# 16nMod4.net
KiCad netlist of a schematic drawn in EAGLE
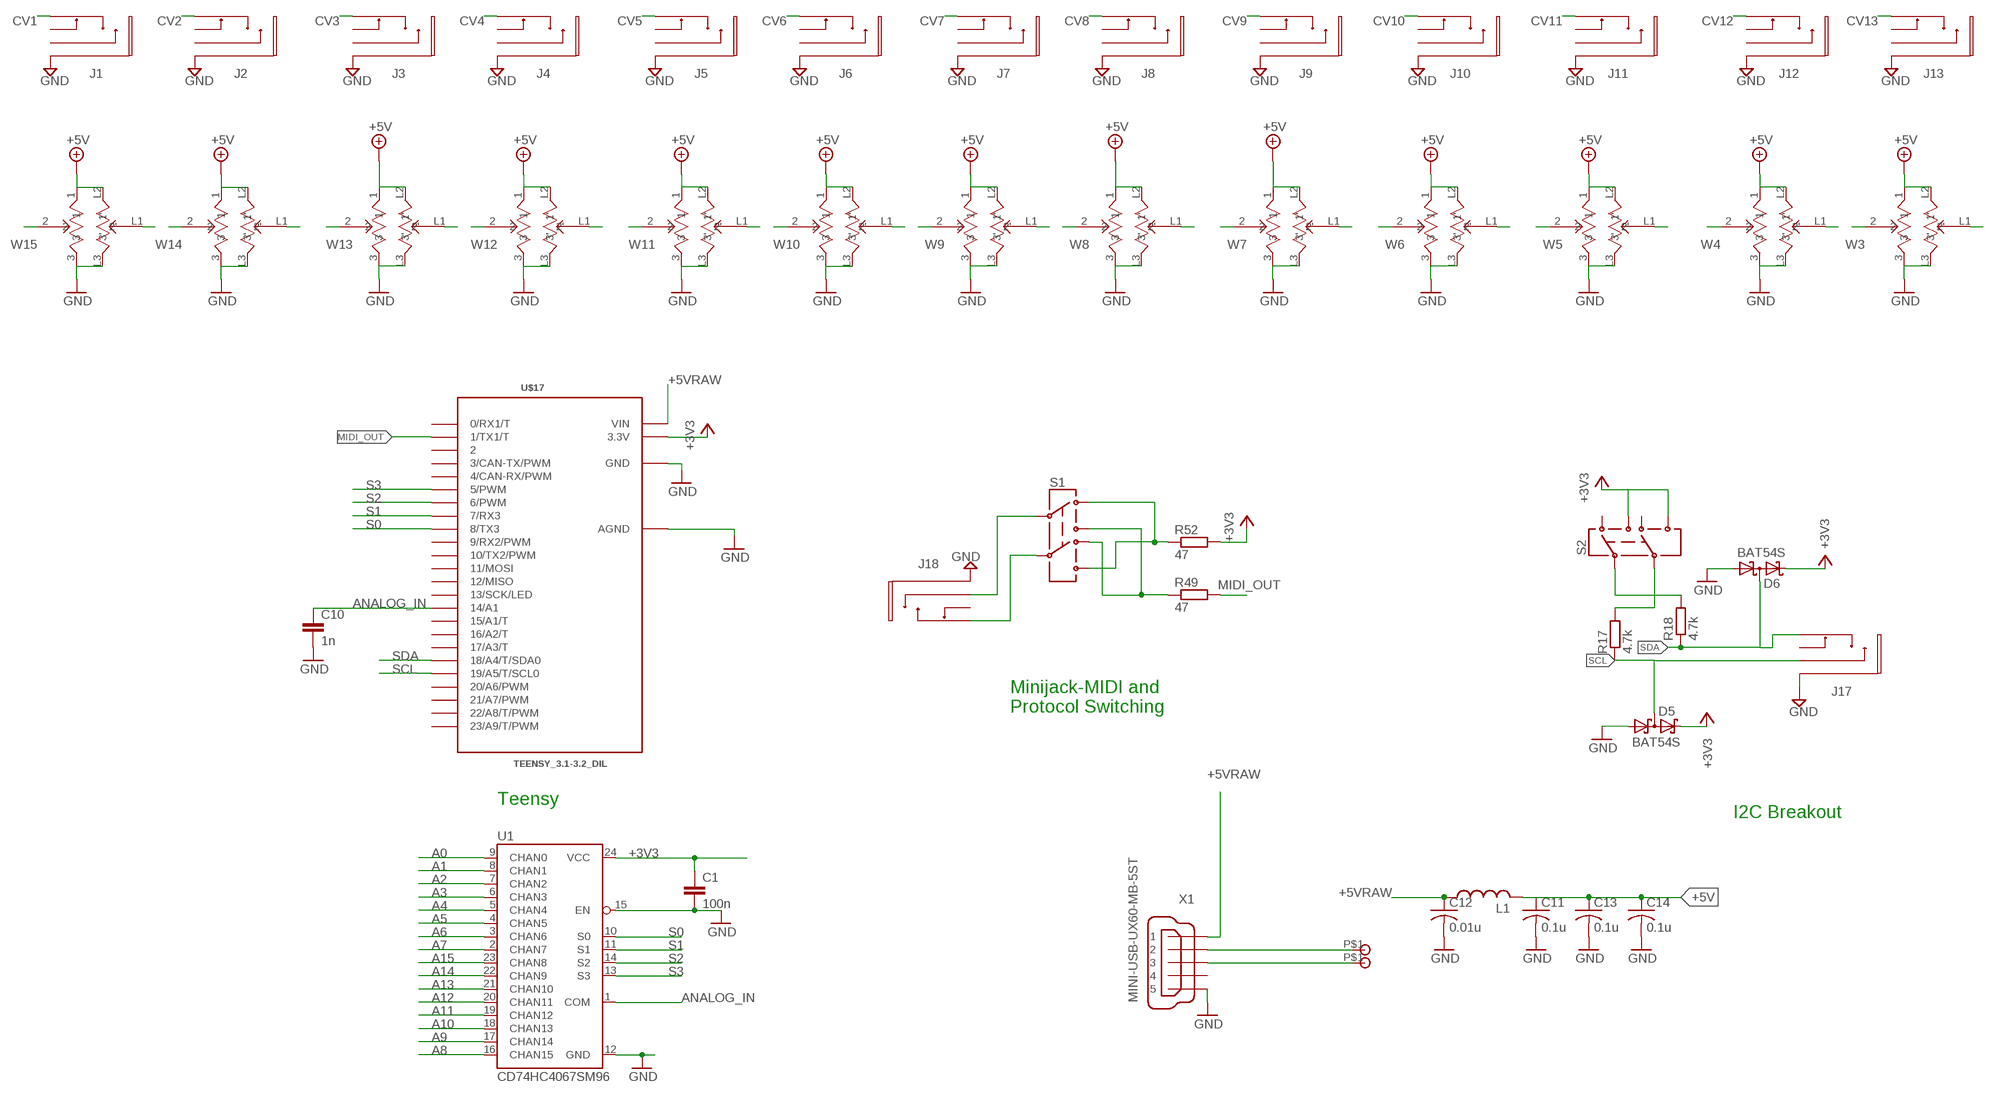
[diagram p0: schematic, sheet 1, part 1 of 2]
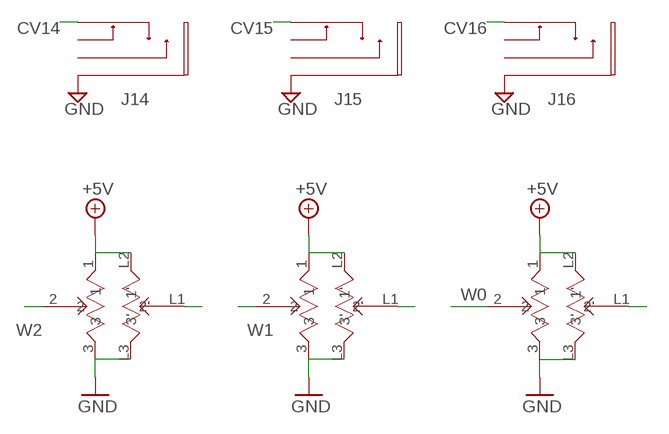
[diagram p1: schematic, sheet 1, part 2 of 2]
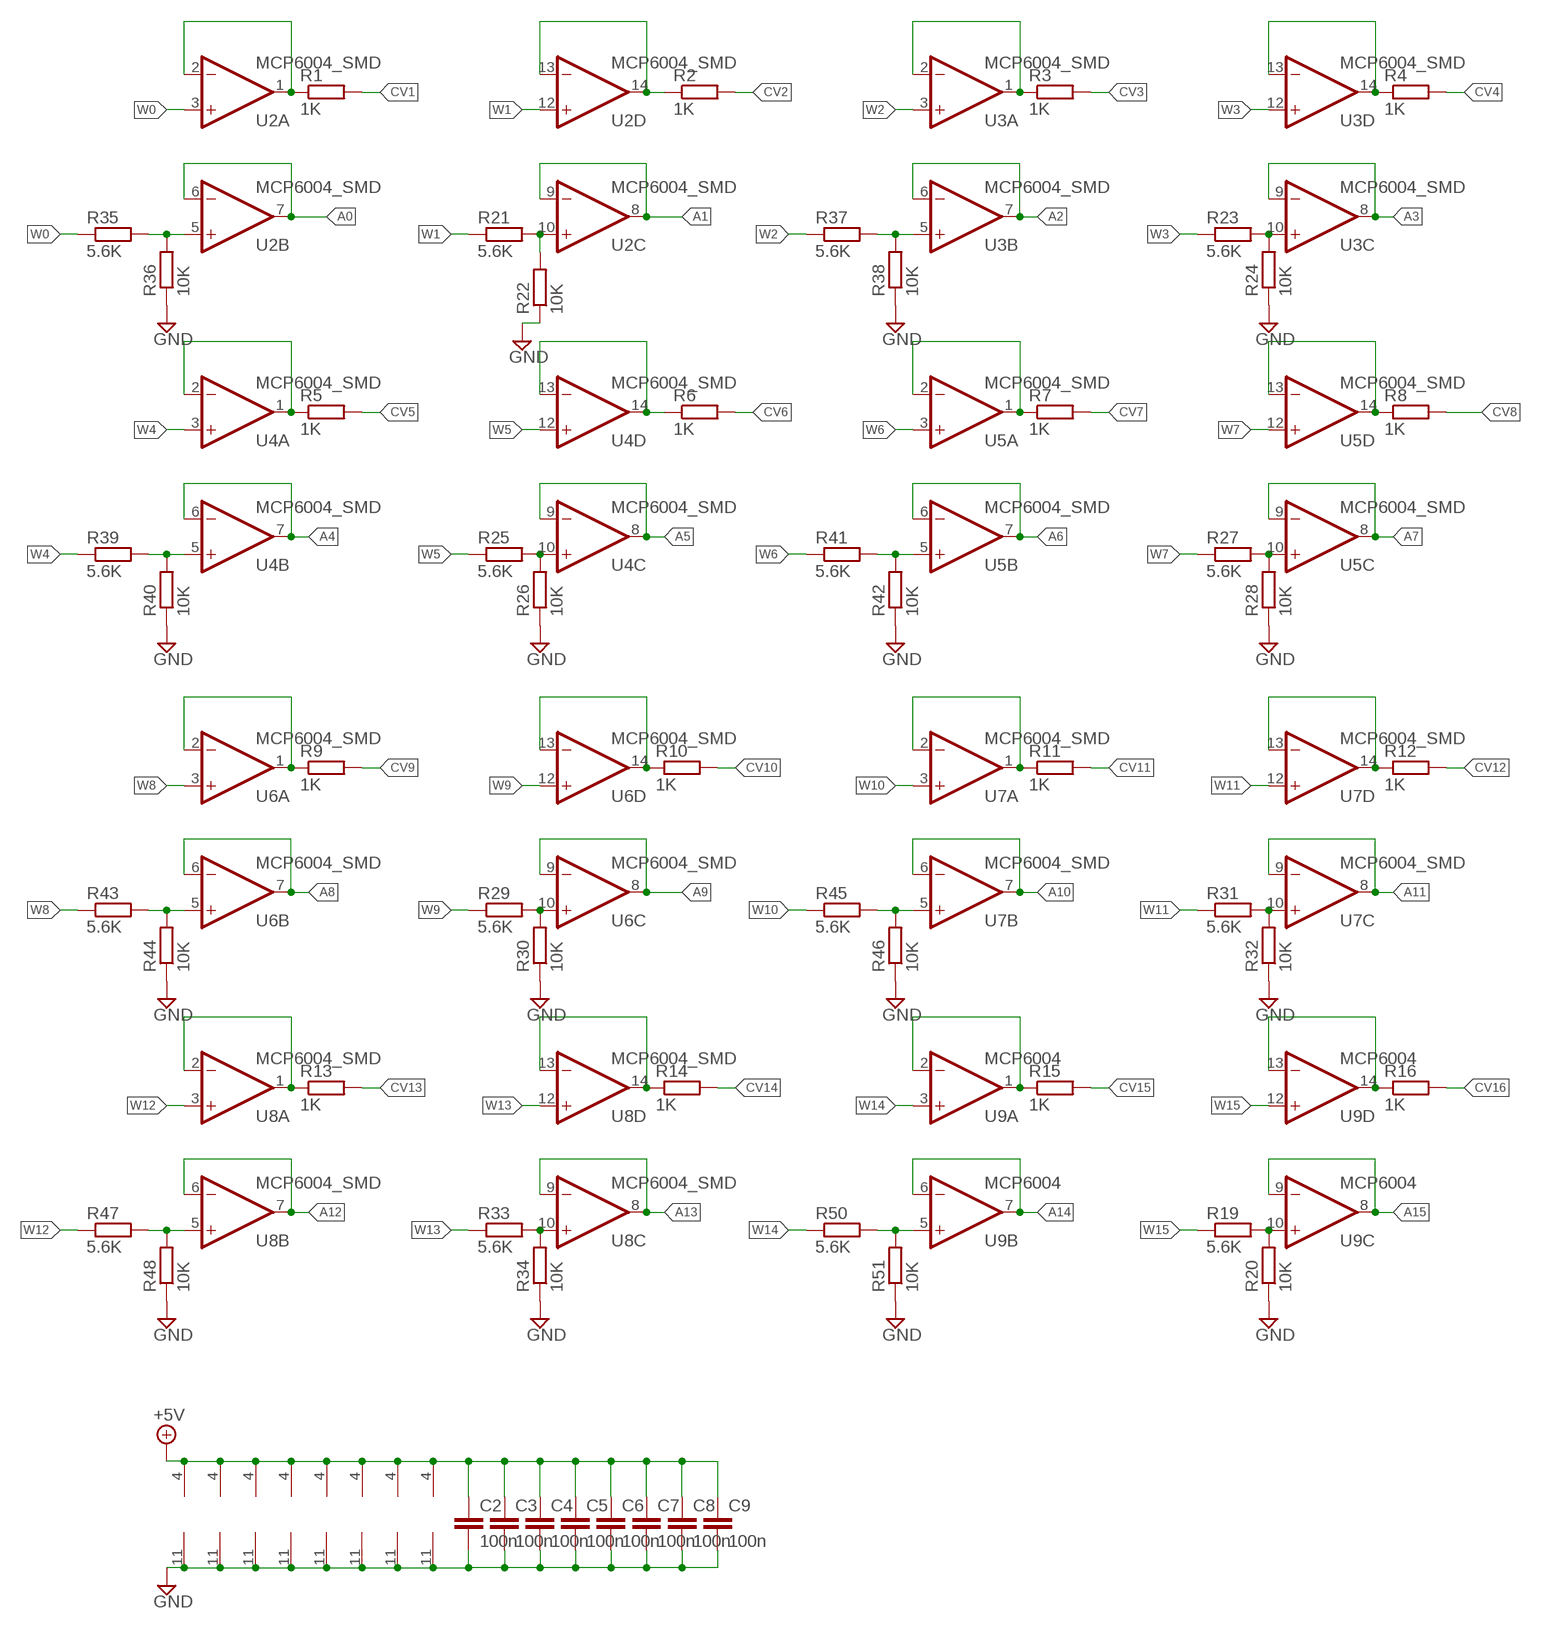
[diagram p2: schematic, sheet 2]

(export (version "E")
  (design (tool "Eeschema 10.0.6"))
  (components
    (comp (ref "C1")
      (value "100n")
      (footprint "eagle-import:C0805")
      (libsource (lib "eagle-import") (part "C-EUC0805"))
    )
    (comp (ref "C10")
      (value "1n")
      (footprint "eagle-import:C0805")
      (libsource (lib "eagle-import") (part "C-EUC0805"))
    )
    (comp (ref "C11")
      (value "0.1u")
      (footprint "eagle-import:C0805K")
      (libsource (lib "eagle-import") (part "C-USC0805K"))
    )
    (comp (ref "C12")
      (value "0.01u")
      (footprint "eagle-import:C0805K")
      (libsource (lib "eagle-import") (part "C-USC0805K"))
    )
    (comp (ref "C13")
      (value "0.1u")
      (footprint "eagle-import:C0805K")
      (libsource (lib "eagle-import") (part "C-USC0805K"))
    )
    (comp (ref "C14")
      (value "0.1u")
      (footprint "eagle-import:C0805K")
      (libsource (lib "eagle-import") (part "C-USC0805K"))
    )
    (comp (ref "D5")
      (value "BAT54S")
      (footprint "eagle-import:SOT23")
      (libsource (lib "eagle-import") (part "BAT54S"))
    )
    (comp (ref "D6")
      (value "BAT54S")
      (footprint "eagle-import:SOT23")
      (libsource (lib "eagle-import") (part "BAT54S"))
    )
    (comp (ref "J1")
      (value "PJ327E")
      (footprint "eagle-import:PJ327")
      (libsource (lib "eagle-import") (part "PJ327E"))
    )
    (comp (ref "J2")
      (value "PJ327E")
      (footprint "eagle-import:PJ327")
      (libsource (lib "eagle-import") (part "PJ327E"))
    )
    (comp (ref "J3")
      (value "PJ327E")
      (footprint "eagle-import:PJ327")
      (libsource (lib "eagle-import") (part "PJ327E"))
    )
    (comp (ref "J4")
      (value "PJ327E")
      (footprint "eagle-import:PJ327")
      (libsource (lib "eagle-import") (part "PJ327E"))
    )
    (comp (ref "J5")
      (value "PJ327E")
      (footprint "eagle-import:PJ327")
      (libsource (lib "eagle-import") (part "PJ327E"))
    )
    (comp (ref "J6")
      (value "PJ327E")
      (footprint "eagle-import:PJ327")
      (libsource (lib "eagle-import") (part "PJ327E"))
    )
    (comp (ref "J7")
      (value "PJ327E")
      (footprint "eagle-import:PJ327")
      (libsource (lib "eagle-import") (part "PJ327E"))
    )
    (comp (ref "J8")
      (value "PJ327E")
      (footprint "eagle-import:PJ327")
      (libsource (lib "eagle-import") (part "PJ327E"))
    )
    (comp (ref "J9")
      (value "PJ327E")
      (footprint "eagle-import:PJ327")
      (libsource (lib "eagle-import") (part "PJ327E"))
    )
    (comp (ref "J10")
      (value "PJ327E")
      (footprint "eagle-import:PJ327")
      (libsource (lib "eagle-import") (part "PJ327E"))
    )
    (comp (ref "J11")
      (value "PJ327E")
      (footprint "eagle-import:PJ327")
      (libsource (lib "eagle-import") (part "PJ327E"))
    )
    (comp (ref "J12")
      (value "PJ327E")
      (footprint "eagle-import:PJ327")
      (libsource (lib "eagle-import") (part "PJ327E"))
    )
    (comp (ref "J13")
      (value "PJ327E")
      (footprint "eagle-import:PJ327")
      (libsource (lib "eagle-import") (part "PJ327E"))
    )
    (comp (ref "J14")
      (value "PJ327E")
      (footprint "eagle-import:PJ327")
      (libsource (lib "eagle-import") (part "PJ327E"))
    )
    (comp (ref "J15")
      (value "PJ327E")
      (footprint "eagle-import:PJ327")
      (libsource (lib "eagle-import") (part "PJ327E"))
    )
    (comp (ref "J16")
      (value "PJ327E")
      (footprint "eagle-import:PJ327")
      (libsource (lib "eagle-import") (part "PJ327E"))
    )
    (comp (ref "J17")
      (value "PJ327E")
      (footprint "eagle-import:PJ327")
      (libsource (lib "eagle-import") (part "PJ327E"))
    )
    (comp (ref "J18")
      (value "PJ327E")
      (footprint "eagle-import:PJ327")
      (libsource (lib "eagle-import") (part "PJ327E"))
    )
    (comp (ref "L1")
      (value "L-USL2012C")
      (footprint "eagle-import:L2012C")
      (libsource (lib "eagle-import") (part "L-USL2012C"))
    )
    (comp (ref "R17")
      (value "4.7k")
      (footprint "eagle-import:R0805")
      (libsource (lib "eagle-import") (part "R-EU_R0805"))
    )
    (comp (ref "R18")
      (value "4.7k")
      (footprint "eagle-import:R0805")
      (libsource (lib "eagle-import") (part "R-EU_R0805"))
    )
    (comp (ref "R49")
      (value "47")
      (footprint "eagle-import:R0805")
      (libsource (lib "eagle-import") (part "R-EU_R0805"))
    )
    (comp (ref "R52")
      (value "47")
      (footprint "eagle-import:R0805")
      (libsource (lib "eagle-import") (part "R-EU_R0805"))
    )
    (comp (ref "S1")
      (value "SWITCH-DPDT")
      (footprint "eagle-import:JS202011JAQN")
      (libsource (lib "eagle-import") (part "SWITCH-DPDT"))
    )
    (comp (ref "S2")
      (value "SWITCH-DPDT")
      (footprint "eagle-import:JS202011JAQN")
      (libsource (lib "eagle-import") (part "SWITCH-DPDT"))
    )
    (comp (ref "U$1")
      (value "SLIDEPOT-ALPS-60MM")
      (footprint "eagle-import:RS6011SP600")
      (libsource (lib "eagle-import") (part "SLIDEPOT-ALPS-60MM"))
    )
    (comp (ref "U$2")
      (value "SLIDEPOT-ALPS-60MM")
      (footprint "eagle-import:RS6011SP600")
      (libsource (lib "eagle-import") (part "SLIDEPOT-ALPS-60MM"))
    )
    (comp (ref "U$3")
      (value "SLIDEPOT-ALPS-60MM")
      (footprint "eagle-import:RS6011SP600")
      (libsource (lib "eagle-import") (part "SLIDEPOT-ALPS-60MM"))
    )
    (comp (ref "U$4")
      (value "SLIDEPOT-ALPS-60MM")
      (footprint "eagle-import:RS6011SP600")
      (libsource (lib "eagle-import") (part "SLIDEPOT-ALPS-60MM"))
    )
    (comp (ref "U$5")
      (value "SLIDEPOT-ALPS-60MM")
      (footprint "eagle-import:RS6011SP600")
      (libsource (lib "eagle-import") (part "SLIDEPOT-ALPS-60MM"))
    )
    (comp (ref "U$6")
      (value "SLIDEPOT-ALPS-60MM")
      (footprint "eagle-import:RS6011SP600")
      (libsource (lib "eagle-import") (part "SLIDEPOT-ALPS-60MM"))
    )
    (comp (ref "U$7")
      (value "SLIDEPOT-ALPS-60MM")
      (footprint "eagle-import:RS6011SP600")
      (libsource (lib "eagle-import") (part "SLIDEPOT-ALPS-60MM"))
    )
    (comp (ref "U$8")
      (value "SLIDEPOT-ALPS-60MM")
      (footprint "eagle-import:RS6011SP600")
      (libsource (lib "eagle-import") (part "SLIDEPOT-ALPS-60MM"))
    )
    (comp (ref "U$9")
      (value "SLIDEPOT-ALPS-60MM")
      (footprint "eagle-import:RS6011SP600")
      (libsource (lib "eagle-import") (part "SLIDEPOT-ALPS-60MM"))
    )
    (comp (ref "U$10")
      (value "SLIDEPOT-ALPS-60MM")
      (footprint "eagle-import:RS6011SP600")
      (libsource (lib "eagle-import") (part "SLIDEPOT-ALPS-60MM"))
    )
    (comp (ref "U$11")
      (value "SLIDEPOT-ALPS-60MM")
      (footprint "eagle-import:RS6011SP600")
      (libsource (lib "eagle-import") (part "SLIDEPOT-ALPS-60MM"))
    )
    (comp (ref "U$12")
      (value "SLIDEPOT-ALPS-60MM")
      (footprint "eagle-import:RS6011SP600")
      (libsource (lib "eagle-import") (part "SLIDEPOT-ALPS-60MM"))
    )
    (comp (ref "U$13")
      (value "SLIDEPOT-ALPS-60MM")
      (footprint "eagle-import:RS6011SP600")
      (libsource (lib "eagle-import") (part "SLIDEPOT-ALPS-60MM"))
    )
    (comp (ref "U$14")
      (value "SLIDEPOT-ALPS-60MM")
      (footprint "eagle-import:RS6011SP600")
      (libsource (lib "eagle-import") (part "SLIDEPOT-ALPS-60MM"))
    )
    (comp (ref "U$15")
      (value "SLIDEPOT-ALPS-60MM")
      (footprint "eagle-import:RS6011SP600")
      (libsource (lib "eagle-import") (part "SLIDEPOT-ALPS-60MM"))
    )
    (comp (ref "U$16")
      (value "SLIDEPOT-ALPS-60MM")
      (footprint "eagle-import:RS6011SP600")
      (libsource (lib "eagle-import") (part "SLIDEPOT-ALPS-60MM"))
    )
    (comp (ref "U$17")
      (value "TEENSY_3.1-3.2_DIL")
      (footprint "eagle-import:TEENSY_3.0-3.2&LC_DIL")
      (libsource (lib "eagle-import") (part "TEENSY_3.1-3.2_DIL"))
    )
    (comp (ref "U$19")
      (value "POGO1X")
      (footprint "eagle-import:POGO2MM")
      (libsource (lib "eagle-import") (part "POGO1X"))
    )
    (comp (ref "U$20")
      (value "POGO1X")
      (footprint "eagle-import:POGO2MM")
      (libsource (lib "eagle-import") (part "POGO1X"))
    )
    (comp (ref "U1")
      (value "CD74HC4067SM96")
      (footprint "eagle-import:SOIC127P1030X265-24")
      (libsource (lib "eagle-import") (part "744067SO24"))
    )
    (comp (ref "X1")
      (value "MINI-USB-UX60-MB-5ST")
      (footprint "eagle-import:UX60-MB-5ST")
      (libsource (lib "eagle-import") (part "MINI-USB-UX60-MB-5ST"))
    )
    (comp (ref "C2")
      (value "100n")
      (footprint "eagle-import:C0805")
      (libsource (lib "eagle-import") (part "C-EUC0805"))
    )
    (comp (ref "C3")
      (value "100n")
      (footprint "eagle-import:C0805")
      (libsource (lib "eagle-import") (part "C-EUC0805"))
    )
    (comp (ref "C4")
      (value "100n")
      (footprint "eagle-import:C0805")
      (libsource (lib "eagle-import") (part "C-EUC0805"))
    )
    (comp (ref "C5")
      (value "100n")
      (footprint "eagle-import:C0805")
      (libsource (lib "eagle-import") (part "C-EUC0805"))
    )
    (comp (ref "C6")
      (value "100n")
      (footprint "eagle-import:C0805")
      (libsource (lib "eagle-import") (part "C-EUC0805"))
    )
    (comp (ref "C7")
      (value "100n")
      (footprint "eagle-import:C0805")
      (libsource (lib "eagle-import") (part "C-EUC0805"))
    )
    (comp (ref "C8")
      (value "100n")
      (footprint "eagle-import:C0805")
      (libsource (lib "eagle-import") (part "C-EUC0805"))
    )
    (comp (ref "C9")
      (value "100n")
      (footprint "eagle-import:C0805")
      (libsource (lib "eagle-import") (part "C-EUC0805"))
    )
    (comp (ref "R1")
      (value "1K")
      (footprint "eagle-import:R0805")
      (libsource (lib "eagle-import") (part "R-EU_R0805"))
    )
    (comp (ref "R2")
      (value "1K")
      (footprint "eagle-import:R0805")
      (libsource (lib "eagle-import") (part "R-EU_R0805"))
    )
    (comp (ref "R3")
      (value "1K")
      (footprint "eagle-import:R0805")
      (libsource (lib "eagle-import") (part "R-EU_R0805"))
    )
    (comp (ref "R4")
      (value "1K")
      (footprint "eagle-import:R0805")
      (libsource (lib "eagle-import") (part "R-EU_R0805"))
    )
    (comp (ref "R5")
      (value "1K")
      (footprint "eagle-import:R0805")
      (libsource (lib "eagle-import") (part "R-EU_R0805"))
    )
    (comp (ref "R6")
      (value "1K")
      (footprint "eagle-import:R0805")
      (libsource (lib "eagle-import") (part "R-EU_R0805"))
    )
    (comp (ref "R7")
      (value "1K")
      (footprint "eagle-import:R0805")
      (libsource (lib "eagle-import") (part "R-EU_R0805"))
    )
    (comp (ref "R8")
      (value "1K")
      (footprint "eagle-import:R0805")
      (libsource (lib "eagle-import") (part "R-EU_R0805"))
    )
    (comp (ref "R9")
      (value "1K")
      (footprint "eagle-import:R0805")
      (libsource (lib "eagle-import") (part "R-EU_R0805"))
    )
    (comp (ref "R10")
      (value "1K")
      (footprint "eagle-import:R0805")
      (libsource (lib "eagle-import") (part "R-EU_R0805"))
    )
    (comp (ref "R11")
      (value "1K")
      (footprint "eagle-import:R0805")
      (libsource (lib "eagle-import") (part "R-EU_R0805"))
    )
    (comp (ref "R12")
      (value "1K")
      (footprint "eagle-import:R0805")
      (libsource (lib "eagle-import") (part "R-EU_R0805"))
    )
    (comp (ref "R13")
      (value "1K")
      (footprint "eagle-import:R0805")
      (libsource (lib "eagle-import") (part "R-EU_R0805"))
    )
    (comp (ref "R14")
      (value "1K")
      (footprint "eagle-import:R0805")
      (libsource (lib "eagle-import") (part "R-EU_R0805"))
    )
    (comp (ref "R15")
      (value "1K")
      (footprint "eagle-import:R0805")
      (libsource (lib "eagle-import") (part "R-EU_R0805"))
    )
    (comp (ref "R16")
      (value "1K")
      (footprint "eagle-import:R0805")
      (libsource (lib "eagle-import") (part "R-EU_R0805"))
    )
    (comp (ref "R19")
      (value "5.6K")
      (footprint "eagle-import:R0805")
      (libsource (lib "eagle-import") (part "R-EU_R0805"))
    )
    (comp (ref "R20")
      (value "10K")
      (footprint "eagle-import:R0805")
      (libsource (lib "eagle-import") (part "R-EU_R0805"))
    )
    (comp (ref "R21")
      (value "5.6K")
      (footprint "eagle-import:R0805")
      (libsource (lib "eagle-import") (part "R-EU_R0805"))
    )
    (comp (ref "R22")
      (value "10K")
      (footprint "eagle-import:R0805")
      (libsource (lib "eagle-import") (part "R-EU_R0805"))
    )
    (comp (ref "R23")
      (value "5.6K")
      (footprint "eagle-import:R0805")
      (libsource (lib "eagle-import") (part "R-EU_R0805"))
    )
    (comp (ref "R24")
      (value "10K")
      (footprint "eagle-import:R0805")
      (libsource (lib "eagle-import") (part "R-EU_R0805"))
    )
    (comp (ref "R25")
      (value "5.6K")
      (footprint "eagle-import:R0805")
      (libsource (lib "eagle-import") (part "R-EU_R0805"))
    )
    (comp (ref "R26")
      (value "10K")
      (footprint "eagle-import:R0805")
      (libsource (lib "eagle-import") (part "R-EU_R0805"))
    )
    (comp (ref "R27")
      (value "5.6K")
      (footprint "eagle-import:R0805")
      (libsource (lib "eagle-import") (part "R-EU_R0805"))
    )
    (comp (ref "R28")
      (value "10K")
      (footprint "eagle-import:R0805")
      (libsource (lib "eagle-import") (part "R-EU_R0805"))
    )
    (comp (ref "R29")
      (value "5.6K")
      (footprint "eagle-import:R0805")
      (libsource (lib "eagle-import") (part "R-EU_R0805"))
    )
    (comp (ref "R30")
      (value "10K")
      (footprint "eagle-import:R0805")
      (libsource (lib "eagle-import") (part "R-EU_R0805"))
    )
    (comp (ref "R31")
      (value "5.6K")
      (footprint "eagle-import:R0805")
      (libsource (lib "eagle-import") (part "R-EU_R0805"))
    )
    (comp (ref "R32")
      (value "10K")
      (footprint "eagle-import:R0805")
      (libsource (lib "eagle-import") (part "R-EU_R0805"))
    )
    (comp (ref "R33")
      (value "5.6K")
      (footprint "eagle-import:R0805")
      (libsource (lib "eagle-import") (part "R-EU_R0805"))
    )
    (comp (ref "R34")
      (value "10K")
      (footprint "eagle-import:R0805")
      (libsource (lib "eagle-import") (part "R-EU_R0805"))
    )
    (comp (ref "R35")
      (value "5.6K")
      (footprint "eagle-import:R0805")
      (libsource (lib "eagle-import") (part "R-EU_R0805"))
    )
    (comp (ref "R36")
      (value "10K")
      (footprint "eagle-import:R0805")
      (libsource (lib "eagle-import") (part "R-EU_R0805"))
    )
    (comp (ref "R37")
      (value "5.6K")
      (footprint "eagle-import:R0805")
      (libsource (lib "eagle-import") (part "R-EU_R0805"))
    )
    (comp (ref "R38")
      (value "10K")
      (footprint "eagle-import:R0805")
      (libsource (lib "eagle-import") (part "R-EU_R0805"))
    )
    (comp (ref "R39")
      (value "5.6K")
      (footprint "eagle-import:R0805")
      (libsource (lib "eagle-import") (part "R-EU_R0805"))
    )
    (comp (ref "R40")
      (value "10K")
      (footprint "eagle-import:R0805")
      (libsource (lib "eagle-import") (part "R-EU_R0805"))
    )
    (comp (ref "R41")
      (value "5.6K")
      (footprint "eagle-import:R0805")
      (libsource (lib "eagle-import") (part "R-EU_R0805"))
    )
    (comp (ref "R42")
      (value "10K")
      (footprint "eagle-import:R0805")
      (libsource (lib "eagle-import") (part "R-EU_R0805"))
    )
    (comp (ref "R43")
      (value "5.6K")
      (footprint "eagle-import:R0805")
      (libsource (lib "eagle-import") (part "R-EU_R0805"))
    )
    (comp (ref "R44")
      (value "10K")
      (footprint "eagle-import:R0805")
      (libsource (lib "eagle-import") (part "R-EU_R0805"))
    )
    (comp (ref "R45")
      (value "5.6K")
      (footprint "eagle-import:R0805")
      (libsource (lib "eagle-import") (part "R-EU_R0805"))
    )
    (comp (ref "R46")
      (value "10K")
      (footprint "eagle-import:R0805")
      (libsource (lib "eagle-import") (part "R-EU_R0805"))
    )
    (comp (ref "R47")
      (value "5.6K")
      (footprint "eagle-import:R0805")
      (libsource (lib "eagle-import") (part "R-EU_R0805"))
    )
    (comp (ref "R48")
      (value "10K")
      (footprint "eagle-import:R0805")
      (libsource (lib "eagle-import") (part "R-EU_R0805"))
    )
    (comp (ref "R50")
      (value "5.6K")
      (footprint "eagle-import:R0805")
      (libsource (lib "eagle-import") (part "R-EU_R0805"))
    )
    (comp (ref "R51")
      (value "10K")
      (footprint "eagle-import:R0805")
      (libsource (lib "eagle-import") (part "R-EU_R0805"))
    )
    (comp (ref "U2")
      (value "MCP6004_SMD")
      (footprint "eagle-import:SO14")
      (libsource (lib "eagle-import") (part "MCP6004_SMD"))
    )
    (comp (ref "U3")
      (value "MCP6004_SMD")
      (footprint "eagle-import:SO14")
      (libsource (lib "eagle-import") (part "MCP6004_SMD"))
    )
    (comp (ref "U4")
      (value "MCP6004_SMD")
      (footprint "eagle-import:SO14")
      (libsource (lib "eagle-import") (part "MCP6004_SMD"))
    )
    (comp (ref "U5")
      (value "MCP6004_SMD")
      (footprint "eagle-import:SO14")
      (libsource (lib "eagle-import") (part "MCP6004_SMD"))
    )
    (comp (ref "U6")
      (value "MCP6004_SMD")
      (footprint "eagle-import:SO14")
      (libsource (lib "eagle-import") (part "MCP6004_SMD"))
    )
    (comp (ref "U7")
      (value "MCP6004_SMD")
      (footprint "eagle-import:SO14")
      (libsource (lib "eagle-import") (part "MCP6004_SMD"))
    )
    (comp (ref "U8")
      (value "MCP6004_SMD")
      (footprint "eagle-import:SO14")
      (libsource (lib "eagle-import") (part "MCP6004_SMD"))
    )
    (comp (ref "U9")
      (value "MCP6004")
      (footprint "eagle-import:SO14")
      (libsource (lib "eagle-import") (part "MCP6004_SMD"))
    )
  )
  (nets
    (net (code "1") (name "+3V3") (class "Default")
      (node (ref "C1") (pin "1") (pinfunction "1_1") (pintype "passive"))
      (node (ref "D5") (pin "2") (pinfunction "2_2") (pintype "passive"))
      (node (ref "D6") (pin "2") (pinfunction "2_2") (pintype "passive"))
      (node (ref "R52") (pin "2") (pinfunction "2_2") (pintype "passive"))
      (node (ref "S2") (pin "P$3") (pinfunction "6_P$3") (pintype "bidirectional"))
      (node (ref "S2") (pin "P$7") (pinfunction "3_P$7") (pintype "bidirectional"))
      (node (ref "U$17") (pin "3.3V") (pinfunction "3.3V_3.3V") (pintype "power_in"))
      (node (ref "U1") (pin "24") (pinfunction "VCC_24") (pintype "bidirectional"))
    )
    (net (code "2") (name "+5V") (class "Default")
      (node (ref "C11") (pin "1") (pinfunction "1_1") (pintype "passive"))
      (node (ref "C13") (pin "1") (pinfunction "1_1") (pintype "passive"))
      (node (ref "C14") (pin "1") (pinfunction "1_1") (pintype "passive"))
      (node (ref "C2") (pin "1") (pinfunction "1_1") (pintype "passive"))
      (node (ref "C3") (pin "1") (pinfunction "1_1") (pintype "passive"))
      (node (ref "C4") (pin "1") (pinfunction "1_1") (pintype "passive"))
      (node (ref "C5") (pin "1") (pinfunction "1_1") (pintype "passive"))
      (node (ref "C6") (pin "1") (pinfunction "1_1") (pintype "passive"))
      (node (ref "C7") (pin "1") (pinfunction "1_1") (pintype "passive"))
      (node (ref "C8") (pin "1") (pinfunction "1_1") (pintype "passive"))
      (node (ref "C9") (pin "1") (pinfunction "1_1") (pintype "passive"))
      (node (ref "L1") (pin "2") (pinfunction "2_2") (pintype "passive"))
      (node (ref "U$1") (pin "1") (pinfunction "1_1") (pintype "bidirectional"))
      (node (ref "U$1") (pin "L2") (pinfunction "1'_L2") (pintype "bidirectional"))
      (node (ref "U$10") (pin "1") (pinfunction "1_1") (pintype "bidirectional"))
      (node (ref "U$10") (pin "L2") (pinfunction "1'_L2") (pintype "bidirectional"))
      (node (ref "U$11") (pin "1") (pinfunction "1_1") (pintype "bidirectional"))
      (node (ref "U$11") (pin "L2") (pinfunction "1'_L2") (pintype "bidirectional"))
      (node (ref "U$12") (pin "1") (pinfunction "1_1") (pintype "bidirectional"))
      (node (ref "U$12") (pin "L2") (pinfunction "1'_L2") (pintype "bidirectional"))
      (node (ref "U$13") (pin "1") (pinfunction "1_1") (pintype "bidirectional"))
      (node (ref "U$13") (pin "L2") (pinfunction "1'_L2") (pintype "bidirectional"))
      (node (ref "U$14") (pin "1") (pinfunction "1_1") (pintype "bidirectional"))
      (node (ref "U$14") (pin "L2") (pinfunction "1'_L2") (pintype "bidirectional"))
      (node (ref "U$15") (pin "1") (pinfunction "1_1") (pintype "bidirectional"))
      (node (ref "U$15") (pin "L2") (pinfunction "1'_L2") (pintype "bidirectional"))
      (node (ref "U$16") (pin "1") (pinfunction "1_1") (pintype "bidirectional"))
      (node (ref "U$16") (pin "L2") (pinfunction "1'_L2") (pintype "bidirectional"))
      (node (ref "U$2") (pin "1") (pinfunction "1_1") (pintype "bidirectional"))
      (node (ref "U$2") (pin "L2") (pinfunction "1'_L2") (pintype "bidirectional"))
      (node (ref "U$3") (pin "1") (pinfunction "1_1") (pintype "bidirectional"))
      (node (ref "U$3") (pin "L2") (pinfunction "1'_L2") (pintype "bidirectional"))
      (node (ref "U$4") (pin "1") (pinfunction "1_1") (pintype "bidirectional"))
      (node (ref "U$4") (pin "L2") (pinfunction "1'_L2") (pintype "bidirectional"))
      (node (ref "U$5") (pin "1") (pinfunction "1_1") (pintype "bidirectional"))
      (node (ref "U$5") (pin "L2") (pinfunction "1'_L2") (pintype "bidirectional"))
      (node (ref "U$6") (pin "1") (pinfunction "1_1") (pintype "bidirectional"))
      (node (ref "U$6") (pin "L2") (pinfunction "1'_L2") (pintype "bidirectional"))
      (node (ref "U$7") (pin "1") (pinfunction "1_1") (pintype "bidirectional"))
      (node (ref "U$7") (pin "L2") (pinfunction "1'_L2") (pintype "bidirectional"))
      (node (ref "U$8") (pin "1") (pinfunction "1_1") (pintype "bidirectional"))
      (node (ref "U$8") (pin "L2") (pinfunction "1'_L2") (pintype "bidirectional"))
      (node (ref "U$9") (pin "1") (pinfunction "1_1") (pintype "bidirectional"))
      (node (ref "U$9") (pin "L2") (pinfunction "1'_L2") (pintype "bidirectional"))
      (node (ref "U2") (pin "4") (pinfunction "V+_4") (pintype "power_in"))
      (node (ref "U3") (pin "4") (pinfunction "V+_4") (pintype "power_in"))
      (node (ref "U4") (pin "4") (pinfunction "V+_4") (pintype "power_in"))
      (node (ref "U5") (pin "4") (pinfunction "V+_4") (pintype "power_in"))
      (node (ref "U6") (pin "4") (pinfunction "V+_4") (pintype "power_in"))
      (node (ref "U7") (pin "4") (pinfunction "V+_4") (pintype "power_in"))
      (node (ref "U8") (pin "4") (pinfunction "V+_4") (pintype "power_in"))
      (node (ref "U9") (pin "4") (pinfunction "V+_4") (pintype "power_in"))
    )
    (net (code "3") (name "+5VRAW") (class "Default")
      (node (ref "C12") (pin "1") (pinfunction "1_1") (pintype "passive"))
      (node (ref "L1") (pin "1") (pinfunction "1_1") (pintype "passive"))
      (node (ref "U$17") (pin "VIN") (pinfunction "VIN_VIN") (pintype "power_in"))
      (node (ref "X1") (pin "1") (pinfunction "1_1") (pintype "input"))
    )
    (net (code "4") (name "A0") (class "Default")
      (node (ref "U1") (pin "9") (pinfunction "CHAN0_9") (pintype "bidirectional"))
      (node (ref "U2") (pin "6") (pinfunction "-IN_6") (pintype "input"))
      (node (ref "U2") (pin "7") (pinfunction "OUT_7") (pintype "output"))
    )
    (net (code "5") (name "A1") (class "Default")
      (node (ref "U1") (pin "8") (pinfunction "CHAN1_8") (pintype "bidirectional"))
      (node (ref "U2") (pin "8") (pinfunction "OUT_8") (pintype "output"))
      (node (ref "U2") (pin "9") (pinfunction "-IN_9") (pintype "input"))
    )
    (net (code "6") (name "A2") (class "Default")
      (node (ref "U1") (pin "7") (pinfunction "CHAN2_7") (pintype "bidirectional"))
      (node (ref "U3") (pin "6") (pinfunction "-IN_6") (pintype "input"))
      (node (ref "U3") (pin "7") (pinfunction "OUT_7") (pintype "output"))
    )
    (net (code "7") (name "A3") (class "Default")
      (node (ref "U1") (pin "6") (pinfunction "CHAN3_6") (pintype "bidirectional"))
      (node (ref "U3") (pin "8") (pinfunction "OUT_8") (pintype "output"))
      (node (ref "U3") (pin "9") (pinfunction "-IN_9") (pintype "input"))
    )
    (net (code "8") (name "A4") (class "Default")
      (node (ref "U1") (pin "5") (pinfunction "CHAN4_5") (pintype "bidirectional"))
      (node (ref "U4") (pin "6") (pinfunction "-IN_6") (pintype "input"))
      (node (ref "U4") (pin "7") (pinfunction "OUT_7") (pintype "output"))
    )
    (net (code "9") (name "A5") (class "Default")
      (node (ref "U1") (pin "4") (pinfunction "CHAN5_4") (pintype "bidirectional"))
      (node (ref "U4") (pin "8") (pinfunction "OUT_8") (pintype "output"))
      (node (ref "U4") (pin "9") (pinfunction "-IN_9") (pintype "input"))
    )
    (net (code "10") (name "A6") (class "Default")
      (node (ref "U1") (pin "3") (pinfunction "CHAN6_3") (pintype "bidirectional"))
      (node (ref "U5") (pin "6") (pinfunction "-IN_6") (pintype "input"))
      (node (ref "U5") (pin "7") (pinfunction "OUT_7") (pintype "output"))
    )
    (net (code "11") (name "A7") (class "Default")
      (node (ref "U1") (pin "2") (pinfunction "CHAN7_2") (pintype "bidirectional"))
      (node (ref "U5") (pin "8") (pinfunction "OUT_8") (pintype "output"))
      (node (ref "U5") (pin "9") (pinfunction "-IN_9") (pintype "input"))
    )
    (net (code "12") (name "A8") (class "Default")
      (node (ref "U1") (pin "16") (pinfunction "CHAN15_16") (pintype "bidirectional"))
      (node (ref "U6") (pin "6") (pinfunction "-IN_6") (pintype "input"))
      (node (ref "U6") (pin "7") (pinfunction "OUT_7") (pintype "output"))
    )
    (net (code "13") (name "A9") (class "Default")
      (node (ref "U1") (pin "17") (pinfunction "CHAN14_17") (pintype "bidirectional"))
      (node (ref "U6") (pin "8") (pinfunction "OUT_8") (pintype "output"))
      (node (ref "U6") (pin "9") (pinfunction "-IN_9") (pintype "input"))
    )
    (net (code "14") (name "A10") (class "Default")
      (node (ref "U1") (pin "18") (pinfunction "CHAN13_18") (pintype "bidirectional"))
      (node (ref "U7") (pin "6") (pinfunction "-IN_6") (pintype "input"))
      (node (ref "U7") (pin "7") (pinfunction "OUT_7") (pintype "output"))
    )
    (net (code "15") (name "A11") (class "Default")
      (node (ref "U1") (pin "19") (pinfunction "CHAN12_19") (pintype "bidirectional"))
      (node (ref "U7") (pin "8") (pinfunction "OUT_8") (pintype "output"))
      (node (ref "U7") (pin "9") (pinfunction "-IN_9") (pintype "input"))
    )
    (net (code "16") (name "A12") (class "Default")
      (node (ref "U1") (pin "20") (pinfunction "CHAN11_20") (pintype "bidirectional"))
      (node (ref "U8") (pin "6") (pinfunction "-IN_6") (pintype "input"))
      (node (ref "U8") (pin "7") (pinfunction "OUT_7") (pintype "output"))
    )
    (net (code "17") (name "A13") (class "Default")
      (node (ref "U1") (pin "21") (pinfunction "CHAN10_21") (pintype "bidirectional"))
      (node (ref "U8") (pin "8") (pinfunction "OUT_8") (pintype "output"))
      (node (ref "U8") (pin "9") (pinfunction "-IN_9") (pintype "input"))
    )
    (net (code "18") (name "A14") (class "Default")
      (node (ref "U1") (pin "22") (pinfunction "CHAN9_22") (pintype "bidirectional"))
      (node (ref "U9") (pin "6") (pinfunction "-IN_6") (pintype "input"))
      (node (ref "U9") (pin "7") (pinfunction "OUT_7") (pintype "output"))
    )
    (net (code "19") (name "A15") (class "Default")
      (node (ref "U1") (pin "23") (pinfunction "CHAN8_23") (pintype "bidirectional"))
      (node (ref "U9") (pin "8") (pinfunction "OUT_8") (pintype "output"))
      (node (ref "U9") (pin "9") (pinfunction "-IN_9") (pintype "input"))
    )
    (net (code "20") (name "ANALOG_IN") (class "Default")
      (node (ref "C10") (pin "1") (pinfunction "1_1") (pintype "passive"))
      (node (ref "U$17") (pin "14/A0") (pinfunction "14/A1_14/A0") (pintype "bidirectional"))
      (node (ref "U1") (pin "1") (pinfunction "COM_1") (pintype "bidirectional"))
    )
    (net (code "21") (name "CV1") (class "Default")
      (node (ref "J1") (pin "P$2") (pinfunction "P$2_P$2") (pintype "bidirectional"))
      (node (ref "R1") (pin "2") (pinfunction "2_2") (pintype "passive"))
    )
    (net (code "22") (name "CV2") (class "Default")
      (node (ref "J2") (pin "P$2") (pinfunction "P$2_P$2") (pintype "bidirectional"))
      (node (ref "R2") (pin "2") (pinfunction "2_2") (pintype "passive"))
    )
    (net (code "23") (name "CV3") (class "Default")
      (node (ref "J3") (pin "P$2") (pinfunction "P$2_P$2") (pintype "bidirectional"))
      (node (ref "R3") (pin "2") (pinfunction "2_2") (pintype "passive"))
    )
    (net (code "24") (name "CV4") (class "Default")
      (node (ref "J4") (pin "P$2") (pinfunction "P$2_P$2") (pintype "bidirectional"))
      (node (ref "R4") (pin "2") (pinfunction "2_2") (pintype "passive"))
    )
    (net (code "25") (name "CV5") (class "Default")
      (node (ref "J5") (pin "P$2") (pinfunction "P$2_P$2") (pintype "bidirectional"))
      (node (ref "R5") (pin "2") (pinfunction "2_2") (pintype "passive"))
    )
    (net (code "26") (name "CV6") (class "Default")
      (node (ref "J6") (pin "P$2") (pinfunction "P$2_P$2") (pintype "bidirectional"))
      (node (ref "R6") (pin "2") (pinfunction "2_2") (pintype "passive"))
    )
    (net (code "27") (name "CV7") (class "Default")
      (node (ref "J7") (pin "P$2") (pinfunction "P$2_P$2") (pintype "bidirectional"))
      (node (ref "R7") (pin "2") (pinfunction "2_2") (pintype "passive"))
    )
    (net (code "28") (name "CV8") (class "Default")
      (node (ref "J8") (pin "P$2") (pinfunction "P$2_P$2") (pintype "bidirectional"))
      (node (ref "R8") (pin "2") (pinfunction "2_2") (pintype "passive"))
    )
    (net (code "29") (name "CV9") (class "Default")
      (node (ref "J9") (pin "P$2") (pinfunction "P$2_P$2") (pintype "bidirectional"))
      (node (ref "R9") (pin "2") (pinfunction "2_2") (pintype "passive"))
    )
    (net (code "30") (name "CV10") (class "Default")
      (node (ref "J10") (pin "P$2") (pinfunction "P$2_P$2") (pintype "bidirectional"))
      (node (ref "R10") (pin "2") (pinfunction "2_2") (pintype "passive"))
    )
    (net (code "31") (name "CV11") (class "Default")
      (node (ref "J11") (pin "P$2") (pinfunction "P$2_P$2") (pintype "bidirectional"))
      (node (ref "R11") (pin "2") (pinfunction "2_2") (pintype "passive"))
    )
    (net (code "32") (name "CV12") (class "Default")
      (node (ref "J12") (pin "P$2") (pinfunction "P$2_P$2") (pintype "bidirectional"))
      (node (ref "R12") (pin "2") (pinfunction "2_2") (pintype "passive"))
    )
    (net (code "33") (name "CV13") (class "Default")
      (node (ref "J13") (pin "P$2") (pinfunction "P$2_P$2") (pintype "bidirectional"))
      (node (ref "R13") (pin "2") (pinfunction "2_2") (pintype "passive"))
    )
    (net (code "34") (name "CV14") (class "Default")
      (node (ref "J14") (pin "P$2") (pinfunction "P$2_P$2") (pintype "bidirectional"))
      (node (ref "R14") (pin "2") (pinfunction "2_2") (pintype "passive"))
    )
    (net (code "35") (name "CV15") (class "Default")
      (node (ref "J15") (pin "P$2") (pinfunction "P$2_P$2") (pintype "bidirectional"))
      (node (ref "R15") (pin "2") (pinfunction "2_2") (pintype "passive"))
    )
    (net (code "36") (name "CV16") (class "Default")
      (node (ref "J16") (pin "P$2") (pinfunction "P$2_P$2") (pintype "bidirectional"))
      (node (ref "R16") (pin "2") (pinfunction "2_2") (pintype "passive"))
    )
    (net (code "37") (name "GND") (class "Default")
      (node (ref "C1") (pin "2") (pinfunction "2_2") (pintype "passive"))
      (node (ref "C10") (pin "2") (pinfunction "2_2") (pintype "passive"))
      (node (ref "C11") (pin "2") (pinfunction "2_2") (pintype "passive"))
      (node (ref "C12") (pin "2") (pinfunction "2_2") (pintype "passive"))
      (node (ref "C13") (pin "2") (pinfunction "2_2") (pintype "passive"))
      (node (ref "C14") (pin "2") (pinfunction "2_2") (pintype "passive"))
      (node (ref "C2") (pin "2") (pinfunction "2_2") (pintype "passive"))
      (node (ref "C3") (pin "2") (pinfunction "2_2") (pintype "passive"))
      (node (ref "C4") (pin "2") (pinfunction "2_2") (pintype "passive"))
      (node (ref "C5") (pin "2") (pinfunction "2_2") (pintype "passive"))
      (node (ref "C6") (pin "2") (pinfunction "2_2") (pintype "passive"))
      (node (ref "C7") (pin "2") (pinfunction "2_2") (pintype "passive"))
      (node (ref "C8") (pin "2") (pinfunction "2_2") (pintype "passive"))
      (node (ref "C9") (pin "2") (pinfunction "2_2") (pintype "passive"))
      (node (ref "D5") (pin "3") (pinfunction "1_3") (pintype "passive"))
      (node (ref "D6") (pin "3") (pinfunction "1_3") (pintype "passive"))
      (node (ref "J1") (pin "P$1") (pinfunction "P$1_P$1") (pintype "bidirectional"))
      (node (ref "J10") (pin "P$1") (pinfunction "P$1_P$1") (pintype "bidirectional"))
      (node (ref "J11") (pin "P$1") (pinfunction "P$1_P$1") (pintype "bidirectional"))
      (node (ref "J12") (pin "P$1") (pinfunction "P$1_P$1") (pintype "bidirectional"))
      (node (ref "J13") (pin "P$1") (pinfunction "P$1_P$1") (pintype "bidirectional"))
      (node (ref "J14") (pin "P$1") (pinfunction "P$1_P$1") (pintype "bidirectional"))
      (node (ref "J15") (pin "P$1") (pinfunction "P$1_P$1") (pintype "bidirectional"))
      (node (ref "J16") (pin "P$1") (pinfunction "P$1_P$1") (pintype "bidirectional"))
      (node (ref "J17") (pin "P$1") (pinfunction "P$1_P$1") (pintype "bidirectional"))
      (node (ref "J18") (pin "P$1") (pinfunction "P$1_P$1") (pintype "bidirectional"))
      (node (ref "J2") (pin "P$1") (pinfunction "P$1_P$1") (pintype "bidirectional"))
      (node (ref "J3") (pin "P$1") (pinfunction "P$1_P$1") (pintype "bidirectional"))
      (node (ref "J4") (pin "P$1") (pinfunction "P$1_P$1") (pintype "bidirectional"))
      (node (ref "J5") (pin "P$1") (pinfunction "P$1_P$1") (pintype "bidirectional"))
      (node (ref "J6") (pin "P$1") (pinfunction "P$1_P$1") (pintype "bidirectional"))
      (node (ref "J7") (pin "P$1") (pinfunction "P$1_P$1") (pintype "bidirectional"))
      (node (ref "J8") (pin "P$1") (pinfunction "P$1_P$1") (pintype "bidirectional"))
      (node (ref "J9") (pin "P$1") (pinfunction "P$1_P$1") (pintype "bidirectional"))
      (node (ref "R20") (pin "1") (pinfunction "1_1") (pintype "passive"))
      (node (ref "R22") (pin "1") (pinfunction "1_1") (pintype "passive"))
      (node (ref "R24") (pin "1") (pinfunction "1_1") (pintype "passive"))
      (node (ref "R26") (pin "1") (pinfunction "1_1") (pintype "passive"))
      (node (ref "R28") (pin "1") (pinfunction "1_1") (pintype "passive"))
      (node (ref "R30") (pin "1") (pinfunction "1_1") (pintype "passive"))
      (node (ref "R32") (pin "1") (pinfunction "1_1") (pintype "passive"))
      (node (ref "R34") (pin "1") (pinfunction "1_1") (pintype "passive"))
      (node (ref "R36") (pin "1") (pinfunction "1_1") (pintype "passive"))
      (node (ref "R38") (pin "1") (pinfunction "1_1") (pintype "passive"))
      (node (ref "R40") (pin "1") (pinfunction "1_1") (pintype "passive"))
      (node (ref "R42") (pin "1") (pinfunction "1_1") (pintype "passive"))
      (node (ref "R44") (pin "1") (pinfunction "1_1") (pintype "passive"))
      (node (ref "R46") (pin "1") (pinfunction "1_1") (pintype "passive"))
      (node (ref "R48") (pin "1") (pinfunction "1_1") (pintype "passive"))
      (node (ref "R51") (pin "1") (pinfunction "1_1") (pintype "passive"))
      (node (ref "U$1") (pin "3") (pinfunction "3_3") (pintype "bidirectional"))
      (node (ref "U$1") (pin "L3") (pinfunction "3'_L3") (pintype "bidirectional"))
      (node (ref "U$10") (pin "3") (pinfunction "3_3") (pintype "bidirectional"))
      (node (ref "U$10") (pin "L3") (pinfunction "3'_L3") (pintype "bidirectional"))
      (node (ref "U$11") (pin "3") (pinfunction "3_3") (pintype "bidirectional"))
      (node (ref "U$11") (pin "L3") (pinfunction "3'_L3") (pintype "bidirectional"))
      (node (ref "U$12") (pin "3") (pinfunction "3_3") (pintype "bidirectional"))
      (node (ref "U$12") (pin "L3") (pinfunction "3'_L3") (pintype "bidirectional"))
      (node (ref "U$13") (pin "3") (pinfunction "3_3") (pintype "bidirectional"))
      (node (ref "U$13") (pin "L3") (pinfunction "3'_L3") (pintype "bidirectional"))
      (node (ref "U$14") (pin "3") (pinfunction "3_3") (pintype "bidirectional"))
      (node (ref "U$14") (pin "L3") (pinfunction "3'_L3") (pintype "bidirectional"))
      (node (ref "U$15") (pin "3") (pinfunction "3_3") (pintype "bidirectional"))
      (node (ref "U$15") (pin "L3") (pinfunction "3'_L3") (pintype "bidirectional"))
      (node (ref "U$16") (pin "3") (pinfunction "3_3") (pintype "bidirectional"))
      (node (ref "U$16") (pin "L3") (pinfunction "3'_L3") (pintype "bidirectional"))
      (node (ref "U$17") (pin "AGND") (pinfunction "AGND_AGND") (pintype "power_in"))
      (node (ref "U$17") (pin "GND") (pinfunction "GND_GND") (pintype "power_in"))
      (node (ref "U$2") (pin "3") (pinfunction "3_3") (pintype "bidirectional"))
      (node (ref "U$2") (pin "L3") (pinfunction "3'_L3") (pintype "bidirectional"))
      (node (ref "U$3") (pin "3") (pinfunction "3_3") (pintype "bidirectional"))
      (node (ref "U$3") (pin "L3") (pinfunction "3'_L3") (pintype "bidirectional"))
      (node (ref "U$4") (pin "3") (pinfunction "3_3") (pintype "bidirectional"))
      (node (ref "U$4") (pin "L3") (pinfunction "3'_L3") (pintype "bidirectional"))
      (node (ref "U$5") (pin "3") (pinfunction "3_3") (pintype "bidirectional"))
      (node (ref "U$5") (pin "L3") (pinfunction "3'_L3") (pintype "bidirectional"))
      (node (ref "U$6") (pin "3") (pinfunction "3_3") (pintype "bidirectional"))
      (node (ref "U$6") (pin "L3") (pinfunction "3'_L3") (pintype "bidirectional"))
      (node (ref "U$7") (pin "3") (pinfunction "3_3") (pintype "bidirectional"))
      (node (ref "U$7") (pin "L3") (pinfunction "3'_L3") (pintype "bidirectional"))
      (node (ref "U$8") (pin "3") (pinfunction "3_3") (pintype "bidirectional"))
      (node (ref "U$8") (pin "L3") (pinfunction "3'_L3") (pintype "bidirectional"))
      (node (ref "U$9") (pin "3") (pinfunction "3_3") (pintype "bidirectional"))
      (node (ref "U$9") (pin "L3") (pinfunction "3'_L3") (pintype "bidirectional"))
      (node (ref "U1") (pin "12") (pinfunction "GND_12") (pintype "bidirectional"))
      (node (ref "U1") (pin "15") (pinfunction "EN_15") (pintype "input"))
      (node (ref "U2") (pin "11") (pinfunction "V-_11") (pintype "power_in"))
      (node (ref "U3") (pin "11") (pinfunction "V-_11") (pintype "power_in"))
      (node (ref "U4") (pin "11") (pinfunction "V-_11") (pintype "power_in"))
      (node (ref "U5") (pin "11") (pinfunction "V-_11") (pintype "power_in"))
      (node (ref "U6") (pin "11") (pinfunction "V-_11") (pintype "power_in"))
      (node (ref "U7") (pin "11") (pinfunction "V-_11") (pintype "power_in"))
      (node (ref "U8") (pin "11") (pinfunction "V-_11") (pintype "power_in"))
      (node (ref "U9") (pin "11") (pinfunction "V-_11") (pintype "power_in"))
      (node (ref "X1") (pin "5") (pinfunction "5_5") (pintype "input"))
    )
    (net (code "38") (name "MIDI_OUT") (class "Default")
      (node (ref "R49") (pin "2") (pinfunction "2_2") (pintype "passive"))
      (node (ref "U$17") (pin "1") (pinfunction "1/TX1/T_1") (pintype "bidirectional"))
    )
    (net (code "39") (name "Net-(S1-1)") (class "Default")
      (node (ref "R52") (pin "1") (pinfunction "1_1") (pintype "passive"))
      (node (ref "S1") (pin "P$3") (pinfunction "6_P$3") (pintype "bidirectional"))
      (node (ref "S1") (pin "P$5") (pinfunction "1_P$5") (pintype "bidirectional"))
    )
    (net (code "40") (name "Net-(S1-2)") (class "Default")
      (node (ref "J18") (pin "P$3") (pinfunction "P$3_P$3") (pintype "bidirectional"))
      (node (ref "S1") (pin "P$6") (pinfunction "2_P$6") (pintype "bidirectional"))
    )
    (net (code "41") (name "Net-(S1-3)") (class "Default")
      (node (ref "R49") (pin "1") (pinfunction "1_1") (pintype "passive"))
      (node (ref "S1") (pin "P$1") (pinfunction "4_P$1") (pintype "bidirectional"))
      (node (ref "S1") (pin "P$7") (pinfunction "3_P$7") (pintype "bidirectional"))
    )
    (net (code "42") (name "Net-(S1-5)") (class "Default")
      (node (ref "J18") (pin "P$2") (pinfunction "P$2_P$2") (pintype "bidirectional"))
      (node (ref "S1") (pin "P$2") (pinfunction "5_P$2") (pintype "bidirectional"))
    )
    (net (code "43") (name "Net-(S2-2)") (class "Default")
      (node (ref "R18") (pin "2") (pinfunction "2_2") (pintype "passive"))
      (node (ref "S2") (pin "P$6") (pinfunction "2_P$6") (pintype "bidirectional"))
    )
    (net (code "44") (name "Net-(S2-5)") (class "Default")
      (node (ref "R17") (pin "2") (pinfunction "2_2") (pintype "passive"))
      (node (ref "S2") (pin "P$2") (pinfunction "5_P$2") (pintype "bidirectional"))
    )
    (net (code "45") (name "Net-(U$19-PadP$1)") (class "Default")
      (node (ref "U$19") (pin "P$1") (pinfunction "P$1_P$1") (pintype "bidirectional"))
      (node (ref "X1") (pin "2") (pinfunction "2_2") (pintype "input"))
    )
    (net (code "46") (name "Net-(U$20-PadP$1)") (class "Default")
      (node (ref "U$20") (pin "P$1") (pinfunction "P$1_P$1") (pintype "bidirectional"))
      (node (ref "X1") (pin "3") (pinfunction "3_3") (pintype "input"))
    )
    (net (code "47") (name "Net-(U2A--IN)") (class "Default")
      (node (ref "R1") (pin "1") (pinfunction "1_1") (pintype "passive"))
      (node (ref "U2") (pin "1") (pinfunction "OUT_1") (pintype "output"))
      (node (ref "U2") (pin "2") (pinfunction "-IN_2") (pintype "input"))
    )
    (net (code "48") (name "Net-(U2B-+IN)") (class "Default")
      (node (ref "R35") (pin "2") (pinfunction "2_2") (pintype "passive"))
      (node (ref "R36") (pin "2") (pinfunction "2_2") (pintype "passive"))
      (node (ref "U2") (pin "5") (pinfunction "+IN_5") (pintype "input"))
    )
    (net (code "49") (name "Net-(U2C-+IN)") (class "Default")
      (node (ref "R21") (pin "2") (pinfunction "2_2") (pintype "passive"))
      (node (ref "R22") (pin "2") (pinfunction "2_2") (pintype "passive"))
      (node (ref "U2") (pin "10") (pinfunction "+IN_10") (pintype "input"))
    )
    (net (code "50") (name "Net-(U2D--IN)") (class "Default")
      (node (ref "R2") (pin "1") (pinfunction "1_1") (pintype "passive"))
      (node (ref "U2") (pin "13") (pinfunction "-IN_13") (pintype "input"))
      (node (ref "U2") (pin "14") (pinfunction "OUT_14") (pintype "output"))
    )
    (net (code "51") (name "Net-(U3A--IN)") (class "Default")
      (node (ref "R3") (pin "1") (pinfunction "1_1") (pintype "passive"))
      (node (ref "U3") (pin "1") (pinfunction "OUT_1") (pintype "output"))
      (node (ref "U3") (pin "2") (pinfunction "-IN_2") (pintype "input"))
    )
    (net (code "52") (name "Net-(U3B-+IN)") (class "Default")
      (node (ref "R37") (pin "2") (pinfunction "2_2") (pintype "passive"))
      (node (ref "R38") (pin "2") (pinfunction "2_2") (pintype "passive"))
      (node (ref "U3") (pin "5") (pinfunction "+IN_5") (pintype "input"))
    )
    (net (code "53") (name "Net-(U3C-+IN)") (class "Default")
      (node (ref "R23") (pin "2") (pinfunction "2_2") (pintype "passive"))
      (node (ref "R24") (pin "2") (pinfunction "2_2") (pintype "passive"))
      (node (ref "U3") (pin "10") (pinfunction "+IN_10") (pintype "input"))
    )
    (net (code "54") (name "Net-(U3D--IN)") (class "Default")
      (node (ref "R4") (pin "1") (pinfunction "1_1") (pintype "passive"))
      (node (ref "U3") (pin "13") (pinfunction "-IN_13") (pintype "input"))
      (node (ref "U3") (pin "14") (pinfunction "OUT_14") (pintype "output"))
    )
    (net (code "55") (name "Net-(U4A--IN)") (class "Default")
      (node (ref "R5") (pin "1") (pinfunction "1_1") (pintype "passive"))
      (node (ref "U4") (pin "1") (pinfunction "OUT_1") (pintype "output"))
      (node (ref "U4") (pin "2") (pinfunction "-IN_2") (pintype "input"))
    )
    (net (code "56") (name "Net-(U4B-+IN)") (class "Default")
      (node (ref "R39") (pin "2") (pinfunction "2_2") (pintype "passive"))
      (node (ref "R40") (pin "2") (pinfunction "2_2") (pintype "passive"))
      (node (ref "U4") (pin "5") (pinfunction "+IN_5") (pintype "input"))
    )
    (net (code "57") (name "Net-(U4C-+IN)") (class "Default")
      (node (ref "R25") (pin "2") (pinfunction "2_2") (pintype "passive"))
      (node (ref "R26") (pin "2") (pinfunction "2_2") (pintype "passive"))
      (node (ref "U4") (pin "10") (pinfunction "+IN_10") (pintype "input"))
    )
    (net (code "58") (name "Net-(U4D--IN)") (class "Default")
      (node (ref "R6") (pin "1") (pinfunction "1_1") (pintype "passive"))
      (node (ref "U4") (pin "13") (pinfunction "-IN_13") (pintype "input"))
      (node (ref "U4") (pin "14") (pinfunction "OUT_14") (pintype "output"))
    )
    (net (code "59") (name "Net-(U5A--IN)") (class "Default")
      (node (ref "R7") (pin "1") (pinfunction "1_1") (pintype "passive"))
      (node (ref "U5") (pin "1") (pinfunction "OUT_1") (pintype "output"))
      (node (ref "U5") (pin "2") (pinfunction "-IN_2") (pintype "input"))
    )
    (net (code "60") (name "Net-(U5B-+IN)") (class "Default")
      (node (ref "R41") (pin "2") (pinfunction "2_2") (pintype "passive"))
      (node (ref "R42") (pin "2") (pinfunction "2_2") (pintype "passive"))
      (node (ref "U5") (pin "5") (pinfunction "+IN_5") (pintype "input"))
    )
    (net (code "61") (name "Net-(U5C-+IN)") (class "Default")
      (node (ref "R27") (pin "2") (pinfunction "2_2") (pintype "passive"))
      (node (ref "R28") (pin "2") (pinfunction "2_2") (pintype "passive"))
      (node (ref "U5") (pin "10") (pinfunction "+IN_10") (pintype "input"))
    )
    (net (code "62") (name "Net-(U5D--IN)") (class "Default")
      (node (ref "R8") (pin "1") (pinfunction "1_1") (pintype "passive"))
      (node (ref "U5") (pin "13") (pinfunction "-IN_13") (pintype "input"))
      (node (ref "U5") (pin "14") (pinfunction "OUT_14") (pintype "output"))
    )
    (net (code "63") (name "Net-(U6A--IN)") (class "Default")
      (node (ref "R9") (pin "1") (pinfunction "1_1") (pintype "passive"))
      (node (ref "U6") (pin "1") (pinfunction "OUT_1") (pintype "output"))
      (node (ref "U6") (pin "2") (pinfunction "-IN_2") (pintype "input"))
    )
    (net (code "64") (name "Net-(U6B-+IN)") (class "Default")
      (node (ref "R43") (pin "2") (pinfunction "2_2") (pintype "passive"))
      (node (ref "R44") (pin "2") (pinfunction "2_2") (pintype "passive"))
      (node (ref "U6") (pin "5") (pinfunction "+IN_5") (pintype "input"))
    )
    (net (code "65") (name "Net-(U6C-+IN)") (class "Default")
      (node (ref "R29") (pin "2") (pinfunction "2_2") (pintype "passive"))
      (node (ref "R30") (pin "2") (pinfunction "2_2") (pintype "passive"))
      (node (ref "U6") (pin "10") (pinfunction "+IN_10") (pintype "input"))
    )
    (net (code "66") (name "Net-(U6D--IN)") (class "Default")
      (node (ref "R10") (pin "1") (pinfunction "1_1") (pintype "passive"))
      (node (ref "U6") (pin "13") (pinfunction "-IN_13") (pintype "input"))
      (node (ref "U6") (pin "14") (pinfunction "OUT_14") (pintype "output"))
    )
    (net (code "67") (name "Net-(U7A--IN)") (class "Default")
      (node (ref "R11") (pin "1") (pinfunction "1_1") (pintype "passive"))
      (node (ref "U7") (pin "1") (pinfunction "OUT_1") (pintype "output"))
      (node (ref "U7") (pin "2") (pinfunction "-IN_2") (pintype "input"))
    )
    (net (code "68") (name "Net-(U7B-+IN)") (class "Default")
      (node (ref "R45") (pin "2") (pinfunction "2_2") (pintype "passive"))
      (node (ref "R46") (pin "2") (pinfunction "2_2") (pintype "passive"))
      (node (ref "U7") (pin "5") (pinfunction "+IN_5") (pintype "input"))
    )
    (net (code "69") (name "Net-(U7C-+IN)") (class "Default")
      (node (ref "R31") (pin "2") (pinfunction "2_2") (pintype "passive"))
      (node (ref "R32") (pin "2") (pinfunction "2_2") (pintype "passive"))
      (node (ref "U7") (pin "10") (pinfunction "+IN_10") (pintype "input"))
    )
    (net (code "70") (name "Net-(U7D--IN)") (class "Default")
      (node (ref "R12") (pin "1") (pinfunction "1_1") (pintype "passive"))
      (node (ref "U7") (pin "13") (pinfunction "-IN_13") (pintype "input"))
      (node (ref "U7") (pin "14") (pinfunction "OUT_14") (pintype "output"))
    )
    (net (code "71") (name "Net-(U8A--IN)") (class "Default")
      (node (ref "R13") (pin "1") (pinfunction "1_1") (pintype "passive"))
      (node (ref "U8") (pin "1") (pinfunction "OUT_1") (pintype "output"))
      (node (ref "U8") (pin "2") (pinfunction "-IN_2") (pintype "input"))
    )
    (net (code "72") (name "Net-(U8B-+IN)") (class "Default")
      (node (ref "R47") (pin "2") (pinfunction "2_2") (pintype "passive"))
      (node (ref "R48") (pin "2") (pinfunction "2_2") (pintype "passive"))
      (node (ref "U8") (pin "5") (pinfunction "+IN_5") (pintype "input"))
    )
    (net (code "73") (name "Net-(U8C-+IN)") (class "Default")
      (node (ref "R33") (pin "2") (pinfunction "2_2") (pintype "passive"))
      (node (ref "R34") (pin "2") (pinfunction "2_2") (pintype "passive"))
      (node (ref "U8") (pin "10") (pinfunction "+IN_10") (pintype "input"))
    )
    (net (code "74") (name "Net-(U8D--IN)") (class "Default")
      (node (ref "R14") (pin "1") (pinfunction "1_1") (pintype "passive"))
      (node (ref "U8") (pin "13") (pinfunction "-IN_13") (pintype "input"))
      (node (ref "U8") (pin "14") (pinfunction "OUT_14") (pintype "output"))
    )
    (net (code "75") (name "Net-(U9A--IN)") (class "Default")
      (node (ref "R15") (pin "1") (pinfunction "1_1") (pintype "passive"))
      (node (ref "U9") (pin "1") (pinfunction "OUT_1") (pintype "output"))
      (node (ref "U9") (pin "2") (pinfunction "-IN_2") (pintype "input"))
    )
    (net (code "76") (name "Net-(U9B-+IN)") (class "Default")
      (node (ref "R50") (pin "2") (pinfunction "2_2") (pintype "passive"))
      (node (ref "R51") (pin "2") (pinfunction "2_2") (pintype "passive"))
      (node (ref "U9") (pin "5") (pinfunction "+IN_5") (pintype "input"))
    )
    (net (code "77") (name "Net-(U9C-+IN)") (class "Default")
      (node (ref "R19") (pin "2") (pinfunction "2_2") (pintype "passive"))
      (node (ref "R20") (pin "2") (pinfunction "2_2") (pintype "passive"))
      (node (ref "U9") (pin "10") (pinfunction "+IN_10") (pintype "input"))
    )
    (net (code "78") (name "Net-(U9D--IN)") (class "Default")
      (node (ref "R16") (pin "1") (pinfunction "1_1") (pintype "passive"))
      (node (ref "U9") (pin "13") (pinfunction "-IN_13") (pintype "input"))
      (node (ref "U9") (pin "14") (pinfunction "OUT_14") (pintype "output"))
    )
    (net (code "79") (name "S0") (class "Default")
      (node (ref "U$17") (pin "8") (pinfunction "8/TX3_8") (pintype "bidirectional"))
      (node (ref "U1") (pin "10") (pinfunction "S0_10") (pintype "input"))
    )
    (net (code "80") (name "S1") (class "Default")
      (node (ref "U$17") (pin "7") (pinfunction "7/RX3_7") (pintype "bidirectional"))
      (node (ref "U1") (pin "11") (pinfunction "S1_11") (pintype "input"))
    )
    (net (code "81") (name "S2") (class "Default")
      (node (ref "U$17") (pin "6") (pinfunction "6/PWM_6") (pintype "bidirectional"))
      (node (ref "U1") (pin "14") (pinfunction "S2_14") (pintype "input"))
    )
    (net (code "82") (name "S3") (class "Default")
      (node (ref "U$17") (pin "5") (pinfunction "5/PWM_5") (pintype "bidirectional"))
      (node (ref "U1") (pin "13") (pinfunction "S3_13") (pintype "input"))
    )
    (net (code "83") (name "SCL") (class "Default")
      (node (ref "D5") (pin "1") (pinfunction "3_1") (pintype "passive"))
      (node (ref "J17") (pin "P$3") (pinfunction "P$3_P$3") (pintype "bidirectional"))
      (node (ref "R17") (pin "1") (pinfunction "1_1") (pintype "passive"))
      (node (ref "U$17") (pin "19/A5") (pinfunction "19/A5/T/SCL0_19/A5") (pintype "bidirectional"))
    )
    (net (code "84") (name "SDA") (class "Default")
      (node (ref "D6") (pin "1") (pinfunction "3_1") (pintype "passive"))
      (node (ref "J17") (pin "P$2") (pinfunction "P$2_P$2") (pintype "bidirectional"))
      (node (ref "R18") (pin "1") (pinfunction "1_1") (pintype "passive"))
      (node (ref "U$17") (pin "18/A4") (pinfunction "18/A4/T/SDA0_18/A4") (pintype "bidirectional"))
    )
    (net (code "85") (name "W0") (class "Default")
      (node (ref "R35") (pin "1") (pinfunction "1_1") (pintype "passive"))
      (node (ref "U$1") (pin "2") (pinfunction "2_2") (pintype "bidirectional"))
      (node (ref "U$1") (pin "L1") (pinfunction "2'_L1") (pintype "bidirectional"))
      (node (ref "U2") (pin "3") (pinfunction "+IN_3") (pintype "input"))
    )
    (net (code "86") (name "W1") (class "Default")
      (node (ref "R21") (pin "1") (pinfunction "1_1") (pintype "passive"))
      (node (ref "U$2") (pin "2") (pinfunction "2_2") (pintype "bidirectional"))
      (node (ref "U$2") (pin "L1") (pinfunction "2'_L1") (pintype "bidirectional"))
      (node (ref "U2") (pin "12") (pinfunction "+IN_12") (pintype "input"))
    )
    (net (code "87") (name "W2") (class "Default")
      (node (ref "R37") (pin "1") (pinfunction "1_1") (pintype "passive"))
      (node (ref "U$3") (pin "2") (pinfunction "2_2") (pintype "bidirectional"))
      (node (ref "U$3") (pin "L1") (pinfunction "2'_L1") (pintype "bidirectional"))
      (node (ref "U3") (pin "3") (pinfunction "+IN_3") (pintype "input"))
    )
    (net (code "88") (name "W3") (class "Default")
      (node (ref "R23") (pin "1") (pinfunction "1_1") (pintype "passive"))
      (node (ref "U$4") (pin "2") (pinfunction "2_2") (pintype "bidirectional"))
      (node (ref "U$4") (pin "L1") (pinfunction "2'_L1") (pintype "bidirectional"))
      (node (ref "U3") (pin "12") (pinfunction "+IN_12") (pintype "input"))
    )
    (net (code "89") (name "W4") (class "Default")
      (node (ref "R39") (pin "1") (pinfunction "1_1") (pintype "passive"))
      (node (ref "U$5") (pin "2") (pinfunction "2_2") (pintype "bidirectional"))
      (node (ref "U$5") (pin "L1") (pinfunction "2'_L1") (pintype "bidirectional"))
      (node (ref "U4") (pin "3") (pinfunction "+IN_3") (pintype "input"))
    )
    (net (code "90") (name "W5") (class "Default")
      (node (ref "R25") (pin "1") (pinfunction "1_1") (pintype "passive"))
      (node (ref "U$6") (pin "2") (pinfunction "2_2") (pintype "bidirectional"))
      (node (ref "U$6") (pin "L1") (pinfunction "2'_L1") (pintype "bidirectional"))
      (node (ref "U4") (pin "12") (pinfunction "+IN_12") (pintype "input"))
    )
    (net (code "91") (name "W6") (class "Default")
      (node (ref "R41") (pin "1") (pinfunction "1_1") (pintype "passive"))
      (node (ref "U$7") (pin "2") (pinfunction "2_2") (pintype "bidirectional"))
      (node (ref "U$7") (pin "L1") (pinfunction "2'_L1") (pintype "bidirectional"))
      (node (ref "U5") (pin "3") (pinfunction "+IN_3") (pintype "input"))
    )
    (net (code "92") (name "W7") (class "Default")
      (node (ref "R27") (pin "1") (pinfunction "1_1") (pintype "passive"))
      (node (ref "U$8") (pin "2") (pinfunction "2_2") (pintype "bidirectional"))
      (node (ref "U$8") (pin "L1") (pinfunction "2'_L1") (pintype "bidirectional"))
      (node (ref "U5") (pin "12") (pinfunction "+IN_12") (pintype "input"))
    )
    (net (code "93") (name "W8") (class "Default")
      (node (ref "R43") (pin "1") (pinfunction "1_1") (pintype "passive"))
      (node (ref "U$9") (pin "2") (pinfunction "2_2") (pintype "bidirectional"))
      (node (ref "U$9") (pin "L1") (pinfunction "2'_L1") (pintype "bidirectional"))
      (node (ref "U6") (pin "3") (pinfunction "+IN_3") (pintype "input"))
    )
    (net (code "94") (name "W9") (class "Default")
      (node (ref "R29") (pin "1") (pinfunction "1_1") (pintype "passive"))
      (node (ref "U$10") (pin "2") (pinfunction "2_2") (pintype "bidirectional"))
      (node (ref "U$10") (pin "L1") (pinfunction "2'_L1") (pintype "bidirectional"))
      (node (ref "U6") (pin "12") (pinfunction "+IN_12") (pintype "input"))
    )
    (net (code "95") (name "W10") (class "Default")
      (node (ref "R45") (pin "1") (pinfunction "1_1") (pintype "passive"))
      (node (ref "U$11") (pin "2") (pinfunction "2_2") (pintype "bidirectional"))
      (node (ref "U$11") (pin "L1") (pinfunction "2'_L1") (pintype "bidirectional"))
      (node (ref "U7") (pin "3") (pinfunction "+IN_3") (pintype "input"))
    )
    (net (code "96") (name "W11") (class "Default")
      (node (ref "R31") (pin "1") (pinfunction "1_1") (pintype "passive"))
      (node (ref "U$12") (pin "2") (pinfunction "2_2") (pintype "bidirectional"))
      (node (ref "U$12") (pin "L1") (pinfunction "2'_L1") (pintype "bidirectional"))
      (node (ref "U7") (pin "12") (pinfunction "+IN_12") (pintype "input"))
    )
    (net (code "97") (name "W12") (class "Default")
      (node (ref "R47") (pin "1") (pinfunction "1_1") (pintype "passive"))
      (node (ref "U$13") (pin "2") (pinfunction "2_2") (pintype "bidirectional"))
      (node (ref "U$13") (pin "L1") (pinfunction "2'_L1") (pintype "bidirectional"))
      (node (ref "U8") (pin "3") (pinfunction "+IN_3") (pintype "input"))
    )
    (net (code "98") (name "W13") (class "Default")
      (node (ref "R33") (pin "1") (pinfunction "1_1") (pintype "passive"))
      (node (ref "U$14") (pin "2") (pinfunction "2_2") (pintype "bidirectional"))
      (node (ref "U$14") (pin "L1") (pinfunction "2'_L1") (pintype "bidirectional"))
      (node (ref "U8") (pin "12") (pinfunction "+IN_12") (pintype "input"))
    )
    (net (code "99") (name "W14") (class "Default")
      (node (ref "R50") (pin "1") (pinfunction "1_1") (pintype "passive"))
      (node (ref "U$15") (pin "2") (pinfunction "2_2") (pintype "bidirectional"))
      (node (ref "U$15") (pin "L1") (pinfunction "2'_L1") (pintype "bidirectional"))
      (node (ref "U9") (pin "3") (pinfunction "+IN_3") (pintype "input"))
    )
    (net (code "100") (name "W15") (class "Default")
      (node (ref "R19") (pin "1") (pinfunction "1_1") (pintype "passive"))
      (node (ref "U$16") (pin "2") (pinfunction "2_2") (pintype "bidirectional"))
      (node (ref "U$16") (pin "L1") (pinfunction "2'_L1") (pintype "bidirectional"))
      (node (ref "U9") (pin "12") (pinfunction "+IN_12") (pintype "input"))
    )
    (net (code "101") (name "unconnected-(J1-PadP$3)") (class "Default")
      (node (ref "J1") (pin "P$3") (pinfunction "P$3_P$3") (pintype "bidirectional"))
    )
    (net (code "102") (name "unconnected-(J1-PadP$5)") (class "Default")
      (node (ref "J1") (pin "P$5") (pinfunction "P$5_P$5") (pintype "bidirectional"))
    )
    (net (code "103") (name "unconnected-(J2-PadP$3)") (class "Default")
      (node (ref "J2") (pin "P$3") (pinfunction "P$3_P$3") (pintype "bidirectional"))
    )
    (net (code "104") (name "unconnected-(J2-PadP$5)") (class "Default")
      (node (ref "J2") (pin "P$5") (pinfunction "P$5_P$5") (pintype "bidirectional"))
    )
    (net (code "105") (name "unconnected-(J3-PadP$3)") (class "Default")
      (node (ref "J3") (pin "P$3") (pinfunction "P$3_P$3") (pintype "bidirectional"))
    )
    (net (code "106") (name "unconnected-(J3-PadP$5)") (class "Default")
      (node (ref "J3") (pin "P$5") (pinfunction "P$5_P$5") (pintype "bidirectional"))
    )
    (net (code "107") (name "unconnected-(J4-PadP$3)") (class "Default")
      (node (ref "J4") (pin "P$3") (pinfunction "P$3_P$3") (pintype "bidirectional"))
    )
    (net (code "108") (name "unconnected-(J4-PadP$5)") (class "Default")
      (node (ref "J4") (pin "P$5") (pinfunction "P$5_P$5") (pintype "bidirectional"))
    )
    (net (code "109") (name "unconnected-(J5-PadP$3)") (class "Default")
      (node (ref "J5") (pin "P$3") (pinfunction "P$3_P$3") (pintype "bidirectional"))
    )
    (net (code "110") (name "unconnected-(J5-PadP$5)") (class "Default")
      (node (ref "J5") (pin "P$5") (pinfunction "P$5_P$5") (pintype "bidirectional"))
    )
    (net (code "111") (name "unconnected-(J6-PadP$3)") (class "Default")
      (node (ref "J6") (pin "P$3") (pinfunction "P$3_P$3") (pintype "bidirectional"))
    )
    (net (code "112") (name "unconnected-(J6-PadP$5)") (class "Default")
      (node (ref "J6") (pin "P$5") (pinfunction "P$5_P$5") (pintype "bidirectional"))
    )
    (net (code "113") (name "unconnected-(J7-PadP$3)") (class "Default")
      (node (ref "J7") (pin "P$3") (pinfunction "P$3_P$3") (pintype "bidirectional"))
    )
    (net (code "114") (name "unconnected-(J7-PadP$5)") (class "Default")
      (node (ref "J7") (pin "P$5") (pinfunction "P$5_P$5") (pintype "bidirectional"))
    )
    (net (code "115") (name "unconnected-(J8-PadP$3)") (class "Default")
      (node (ref "J8") (pin "P$3") (pinfunction "P$3_P$3") (pintype "bidirectional"))
    )
    (net (code "116") (name "unconnected-(J8-PadP$5)") (class "Default")
      (node (ref "J8") (pin "P$5") (pinfunction "P$5_P$5") (pintype "bidirectional"))
    )
    (net (code "117") (name "unconnected-(J9-PadP$3)") (class "Default")
      (node (ref "J9") (pin "P$3") (pinfunction "P$3_P$3") (pintype "bidirectional"))
    )
    (net (code "118") (name "unconnected-(J9-PadP$5)") (class "Default")
      (node (ref "J9") (pin "P$5") (pinfunction "P$5_P$5") (pintype "bidirectional"))
    )
    (net (code "119") (name "unconnected-(J10-PadP$3)") (class "Default")
      (node (ref "J10") (pin "P$3") (pinfunction "P$3_P$3") (pintype "bidirectional"))
    )
    (net (code "120") (name "unconnected-(J10-PadP$5)") (class "Default")
      (node (ref "J10") (pin "P$5") (pinfunction "P$5_P$5") (pintype "bidirectional"))
    )
    (net (code "121") (name "unconnected-(J11-PadP$3)") (class "Default")
      (node (ref "J11") (pin "P$3") (pinfunction "P$3_P$3") (pintype "bidirectional"))
    )
    (net (code "122") (name "unconnected-(J11-PadP$5)") (class "Default")
      (node (ref "J11") (pin "P$5") (pinfunction "P$5_P$5") (pintype "bidirectional"))
    )
    (net (code "123") (name "unconnected-(J12-PadP$3)") (class "Default")
      (node (ref "J12") (pin "P$3") (pinfunction "P$3_P$3") (pintype "bidirectional"))
    )
    (net (code "124") (name "unconnected-(J12-PadP$5)") (class "Default")
      (node (ref "J12") (pin "P$5") (pinfunction "P$5_P$5") (pintype "bidirectional"))
    )
    (net (code "125") (name "unconnected-(J13-PadP$3)") (class "Default")
      (node (ref "J13") (pin "P$3") (pinfunction "P$3_P$3") (pintype "bidirectional"))
    )
    (net (code "126") (name "unconnected-(J13-PadP$5)") (class "Default")
      (node (ref "J13") (pin "P$5") (pinfunction "P$5_P$5") (pintype "bidirectional"))
    )
    (net (code "127") (name "unconnected-(J14-PadP$3)") (class "Default")
      (node (ref "J14") (pin "P$3") (pinfunction "P$3_P$3") (pintype "bidirectional"))
    )
    (net (code "128") (name "unconnected-(J14-PadP$5)") (class "Default")
      (node (ref "J14") (pin "P$5") (pinfunction "P$5_P$5") (pintype "bidirectional"))
    )
    (net (code "129") (name "unconnected-(J15-PadP$3)") (class "Default")
      (node (ref "J15") (pin "P$3") (pinfunction "P$3_P$3") (pintype "bidirectional"))
    )
    (net (code "130") (name "unconnected-(J15-PadP$5)") (class "Default")
      (node (ref "J15") (pin "P$5") (pinfunction "P$5_P$5") (pintype "bidirectional"))
    )
    (net (code "131") (name "unconnected-(J16-PadP$3)") (class "Default")
      (node (ref "J16") (pin "P$3") (pinfunction "P$3_P$3") (pintype "bidirectional"))
    )
    (net (code "132") (name "unconnected-(J16-PadP$5)") (class "Default")
      (node (ref "J16") (pin "P$5") (pinfunction "P$5_P$5") (pintype "bidirectional"))
    )
    (net (code "133") (name "unconnected-(J17-PadP$5)") (class "Default")
      (node (ref "J17") (pin "P$5") (pinfunction "P$5_P$5") (pintype "bidirectional"))
    )
    (net (code "134") (name "unconnected-(J18-PadP$5)") (class "Default")
      (node (ref "J18") (pin "P$5") (pinfunction "P$5_P$5") (pintype "bidirectional"))
    )
    (net (code "135") (name "unconnected-(S2-1-PadP$5)") (class "Default")
      (node (ref "S2") (pin "P$5") (pinfunction "1_P$5") (pintype "bidirectional"))
    )
    (net (code "136") (name "unconnected-(S2-4-PadP$1)") (class "Default")
      (node (ref "S2") (pin "P$1") (pinfunction "4_P$1") (pintype "bidirectional"))
    )
    (net (code "137") (name "unconnected-(U$17-0{slash}RX1{slash}T-Pad0)") (class "Default")
      (node (ref "U$17") (pin "0") (pinfunction "0/RX1/T_0") (pintype "bidirectional"))
    )
    (net (code "138") (name "unconnected-(U$17-3{slash}CAN-TX{slash}PWM-Pad3)") (class "Default")
      (node (ref "U$17") (pin "3") (pinfunction "3/CAN-TX/PWM_3") (pintype "bidirectional"))
    )
    (net (code "139") (name "unconnected-(U$17-4{slash}CAN-RX{slash}PWM-Pad4)") (class "Default")
      (node (ref "U$17") (pin "4") (pinfunction "4/CAN-RX/PWM_4") (pintype "bidirectional"))
    )
    (net (code "140") (name "unconnected-(U$17-9{slash}RX2{slash}PWM-Pad9)") (class "Default")
      (node (ref "U$17") (pin "9") (pinfunction "9/RX2/PWM_9") (pintype "bidirectional"))
    )
    (net (code "141") (name "unconnected-(U$17-10{slash}TX2{slash}PWM-Pad10)") (class "Default")
      (node (ref "U$17") (pin "10") (pinfunction "10/TX2/PWM_10") (pintype "bidirectional"))
    )
    (net (code "142") (name "unconnected-(U$17-11{slash}MOSI-Pad11)") (class "Default")
      (node (ref "U$17") (pin "11") (pinfunction "11/MOSI_11") (pintype "bidirectional"))
    )
    (net (code "143") (name "unconnected-(U$17-12{slash}MISO-Pad12)") (class "Default")
      (node (ref "U$17") (pin "12") (pinfunction "12/MISO_12") (pintype "bidirectional"))
    )
    (net (code "144") (name "unconnected-(U$17-13{slash}SCK{slash}LED-Pad13)") (class "Default")
      (node (ref "U$17") (pin "13") (pinfunction "13/SCK/LED_13") (pintype "bidirectional"))
    )
    (net (code "145") (name "unconnected-(U$17-15{slash}A1{slash}T-Pad15{slash}A1)") (class "Default")
      (node (ref "U$17") (pin "15/A1") (pinfunction "15/A1/T_15/A1") (pintype "bidirectional"))
    )
    (net (code "146") (name "unconnected-(U$17-16{slash}A2{slash}T-Pad16{slash}A2)") (class "Default")
      (node (ref "U$17") (pin "16/A2") (pinfunction "16/A2/T_16/A2") (pintype "bidirectional"))
    )
    (net (code "147") (name "unconnected-(U$17-17{slash}A3{slash}T-Pad17{slash}A3)") (class "Default")
      (node (ref "U$17") (pin "17/A3") (pinfunction "17/A3/T_17/A3") (pintype "bidirectional"))
    )
    (net (code "148") (name "unconnected-(U$17-20{slash}A6{slash}PWM-Pad20{slash}A6)") (class "Default")
      (node (ref "U$17") (pin "20/A6") (pinfunction "20/A6/PWM_20/A6") (pintype "bidirectional"))
    )
    (net (code "149") (name "unconnected-(U$17-21{slash}A7{slash}PWM-Pad21{slash}A7)") (class "Default")
      (node (ref "U$17") (pin "21/A7") (pinfunction "21/A7/PWM_21/A7") (pintype "bidirectional"))
    )
    (net (code "150") (name "unconnected-(U$17-22{slash}A8{slash}T{slash}PWM-Pad22{slash}A8)") (class "Default")
      (node (ref "U$17") (pin "22/A8") (pinfunction "22/A8/T/PWM_22/A8") (pintype "bidirectional"))
    )
    (net (code "151") (name "unconnected-(U$17-23{slash}A9{slash}T{slash}PWM-Pad23{slash}A9)") (class "Default")
      (node (ref "U$17") (pin "23/A9") (pinfunction "23/A9/T/PWM_23/A9") (pintype "bidirectional"))
    )
    (net (code "152") (name "unconnected-(U$17-Pad2)") (class "Default")
      (node (ref "U$17") (pin "2") (pinfunction "2_2") (pintype "bidirectional"))
    )
    (net (code "153") (name "unconnected-(X1-Pad4)") (class "Default")
      (node (ref "X1") (pin "4") (pinfunction "4_4") (pintype "input"))
    )
  )
)
